# rfid1.net
KiCad netlist of a schematic drawn in EAGLE
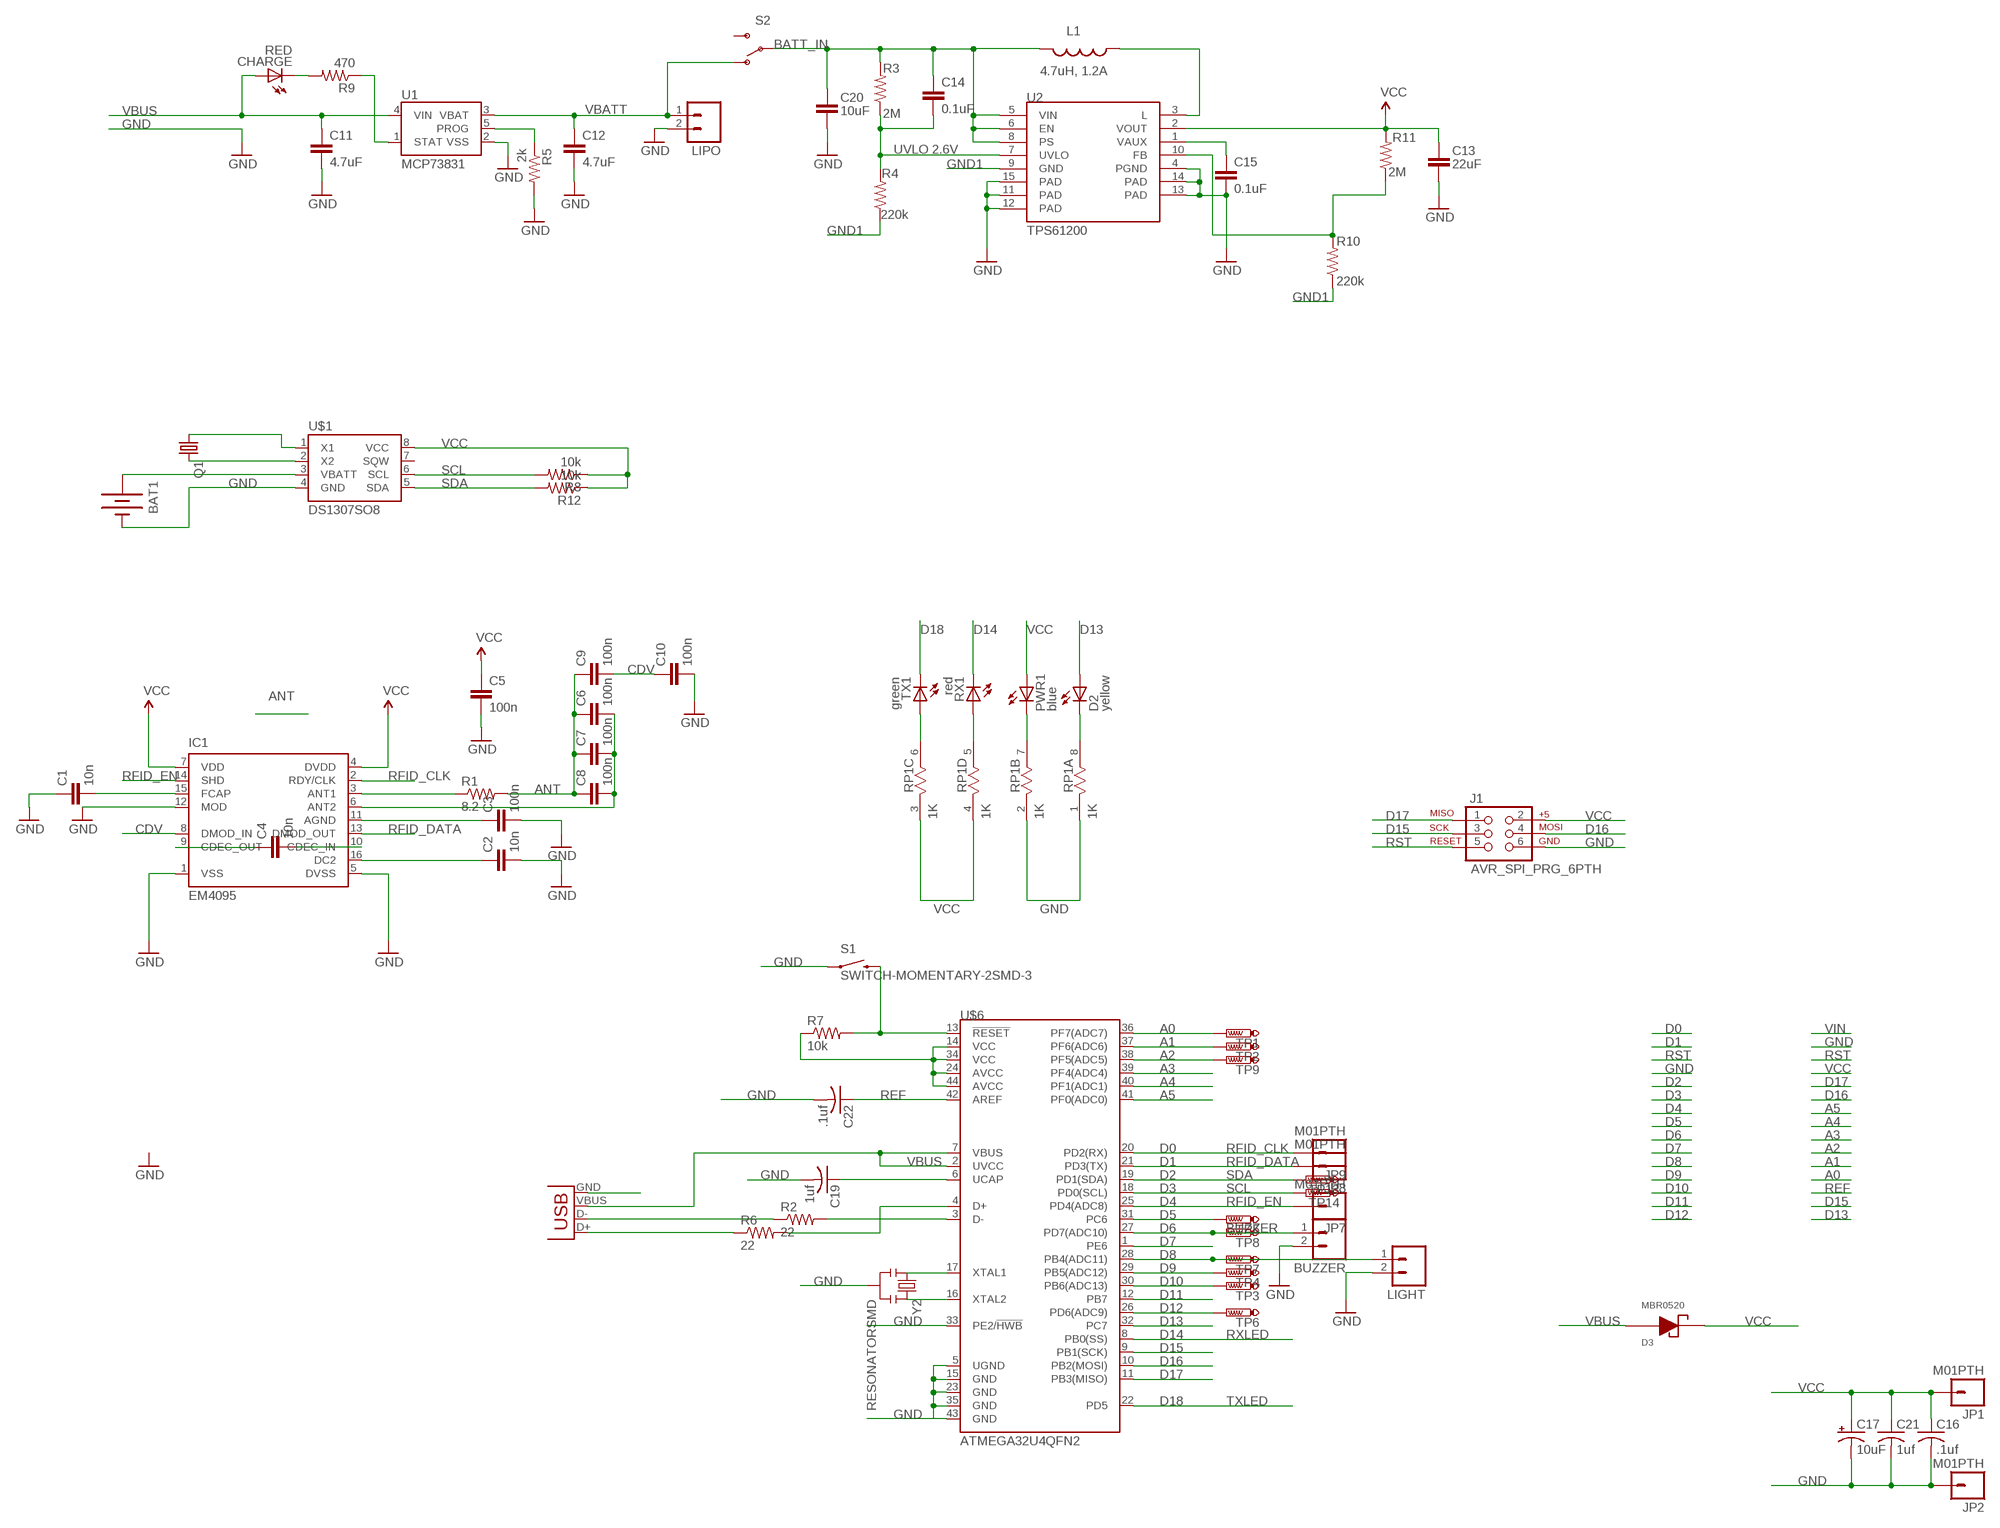
[diagram p0: schematic, sheet 1]

(export (version "E")
  (design (tool "Eeschema 10.0.6"))
  (components
    (comp (ref "BAT1")
      (value "BATTERY12MM")
      (footprint "eagle-import:BATTCON_12MM")
      (libsource (lib "eagle-import") (part "BATTERY12MM"))
    )
    (comp (ref "BUZZER")
      (value "M02PTH")
      (footprint "eagle-import:1X02")
      (libsource (lib "eagle-import") (part "M02PTH"))
    )
    (comp (ref "C1")
      (value "10n")
      (footprint "eagle-import:0805")
      (libsource (lib "eagle-import") (part "SparkFun-Passives_CAP0805"))
    )
    (comp (ref "C2")
      (value "10n")
      (footprint "eagle-import:0805")
      (libsource (lib "eagle-import") (part "SparkFun-Passives_CAP0805"))
    )
    (comp (ref "C3")
      (value "100n")
      (footprint "eagle-import:0805")
      (libsource (lib "eagle-import") (part "SparkFun-Passives_CAP0805"))
    )
    (comp (ref "C4")
      (value "10n")
      (footprint "eagle-import:0805")
      (libsource (lib "eagle-import") (part "SparkFun-Passives_CAP0805"))
    )
    (comp (ref "C5")
      (value "100n")
      (footprint "eagle-import:0805")
      (libsource (lib "eagle-import") (part "SparkFun-Passives_CAP0805"))
    )
    (comp (ref "C6")
      (value "100n")
      (footprint "eagle-import:0805")
      (libsource (lib "eagle-import") (part "SparkFun-Passives_CAP0805"))
    )
    (comp (ref "C7")
      (value "100n")
      (footprint "eagle-import:0805")
      (libsource (lib "eagle-import") (part "SparkFun-Passives_CAP0805"))
    )
    (comp (ref "C8")
      (value "100n")
      (footprint "eagle-import:0805")
      (libsource (lib "eagle-import") (part "SparkFun-Passives_CAP0805"))
    )
    (comp (ref "C9")
      (value "100n")
      (footprint "eagle-import:0805")
      (libsource (lib "eagle-import") (part "SparkFun-Passives_CAP0805"))
    )
    (comp (ref "C10")
      (value "100n")
      (footprint "eagle-import:0805")
      (libsource (lib "eagle-import") (part "SparkFun-Passives_CAP0805"))
    )
    (comp (ref "C11")
      (value "4.7uF")
      (footprint "eagle-import:0603-CAP")
      (libsource (lib "eagle-import") (part "CAP0603-CAP"))
    )
    (comp (ref "C12")
      (value "4.7uF")
      (footprint "eagle-import:0603-CAP")
      (libsource (lib "eagle-import") (part "CAP0603-CAP"))
    )
    (comp (ref "C13")
      (value "22uF")
      (footprint "eagle-import:0805")
      (libsource (lib "eagle-import") (part "CAP0805"))
    )
    (comp (ref "C14")
      (value "0.1uF")
      (footprint "eagle-import:0603-CAP")
      (libsource (lib "eagle-import") (part "CAP0603-CAP"))
    )
    (comp (ref "C15")
      (value "0.1uF")
      (footprint "eagle-import:0603-CAP")
      (libsource (lib "eagle-import") (part "CAP0603-CAP"))
    )
    (comp (ref "C16")
      (value ".1uf")
      (footprint "eagle-import:C0603")
      (libsource (lib "eagle-import") (part "C-USC0603"))
    )
    (comp (ref "C17")
      (value "10uF")
      (footprint "eagle-import:EIA3216")
      (libsource (lib "eagle-import") (part "CAP_POL1206"))
    )
    (comp (ref "C19")
      (value "1uf")
      (footprint "eagle-import:C0603")
      (libsource (lib "eagle-import") (part "C-USC0603"))
    )
    (comp (ref "C20")
      (value "10uF")
      (footprint "eagle-import:1206")
      (libsource (lib "eagle-import") (part "CAP1206"))
    )
    (comp (ref "C21")
      (value "1uf")
      (footprint "eagle-import:C0603")
      (libsource (lib "eagle-import") (part "C-USC0603"))
    )
    (comp (ref "C22")
      (value ".1uf")
      (footprint "eagle-import:C0603")
      (libsource (lib "eagle-import") (part "C-USC0603"))
    )
    (comp (ref "CHARGE")
      (value "RED")
      (footprint "eagle-import:CHIPLED_0805")
      (libsource (lib "eagle-import") (part "LEDCHIPLED_0805"))
    )
    (comp (ref "D2")
      (value "yellow")
      (footprint "eagle-import:CHIPLED_0805")
      (libsource (lib "eagle-import") (part "LEDCHIPLED_0805"))
    )
    (comp (ref "D3")
      (value "MBR0520")
      (footprint "eagle-import:SOD-123")
      (libsource (lib "eagle-import") (part "MBR0520"))
    )
    (comp (ref "IC1")
      (value "EM4095")
      (footprint "eagle-import:SO16")
      (libsource (lib "eagle-import") (part "EM4095"))
    )
    (comp (ref "J1")
      (value "AVR_SPI_PRG_6PTH")
      (footprint "eagle-import:2X3")
      (libsource (lib "eagle-import") (part "AVR_SPI_PRG_6PTH"))
    )
    (comp (ref "JP1")
      (value "M01PTH")
      (footprint "eagle-import:1X01")
      (libsource (lib "eagle-import") (part "M01PTH"))
    )
    (comp (ref "JP2")
      (value "M01PTH")
      (footprint "eagle-import:1X01")
      (libsource (lib "eagle-import") (part "M01PTH"))
    )
    (comp (ref "JP7")
      (value "M01PTH")
      (footprint "eagle-import:1X01")
      (libsource (lib "eagle-import") (part "M01PTH"))
    )
    (comp (ref "JP8")
      (value "M01PTH")
      (footprint "eagle-import:1X01")
      (libsource (lib "eagle-import") (part "M01PTH"))
    )
    (comp (ref "JP9")
      (value "M01PTH")
      (footprint "eagle-import:1X01")
      (libsource (lib "eagle-import") (part "M01PTH"))
    )
    (comp (ref "L1")
      (value "4.7uH, 1.2A")
      (footprint "eagle-import:CDRH2D09")
      (libsource (lib "eagle-import") (part "INDUCTOR."))
    )
    (comp (ref "LIGHT")
      (value "M02PTH")
      (footprint "eagle-import:1X02")
      (libsource (lib "eagle-import") (part "M02PTH"))
    )
    (comp (ref "LIPO")
      (value "M02-JST-2-PTH-NO_SILK")
      (footprint "eagle-import:JST-2-PTH-NS")
      (libsource (lib "eagle-import") (part "M02-JST-2-PTH-NO_SILK"))
    )
    (comp (ref "PWR1")
      (value "blue")
      (footprint "eagle-import:CHIPLED_0805")
      (libsource (lib "eagle-import") (part "LEDCHIPLED_0805"))
    )
    (comp (ref "Q1")
      (value "CRYSTALTC26H")
      (footprint "eagle-import:TC26H")
      (libsource (lib "eagle-import") (part "CRYSTALTC26H"))
    )
    (comp (ref "R1")
      (value "8.2")
      (footprint "eagle-import:0805")
      (libsource (lib "eagle-import") (part "SparkFun-Passives_RESISTOR0805-RES"))
    )
    (comp (ref "R2")
      (value "22")
      (footprint "eagle-import:0603-RES")
      (libsource (lib "eagle-import") (part "RESISTOR0603-RES"))
    )
    (comp (ref "R3")
      (value "2M")
      (footprint "eagle-import:0603-RES")
      (libsource (lib "eagle-import") (part "RESISTOR0603-RES"))
    )
    (comp (ref "R4")
      (value "220k")
      (footprint "eagle-import:0603-RES")
      (libsource (lib "eagle-import") (part "RESISTOR0603-RES"))
    )
    (comp (ref "R5")
      (value "2k")
      (footprint "eagle-import:0603-RES")
      (libsource (lib "eagle-import") (part "RESISTOR0603-RES"))
    )
    (comp (ref "R6")
      (value "22")
      (footprint "eagle-import:0603-RES")
      (libsource (lib "eagle-import") (part "RESISTOR0603-RES"))
    )
    (comp (ref "R7")
      (value "10k")
      (footprint "eagle-import:0603-RES")
      (libsource (lib "eagle-import") (part "RESISTOR0603-RES"))
    )
    (comp (ref "R8")
      (value "10k")
      (footprint "eagle-import:0603-RES")
      (libsource (lib "eagle-import") (part "RESISTOR0603-RES"))
    )
    (comp (ref "R9")
      (value "470")
      (footprint "eagle-import:0603-RES")
      (libsource (lib "eagle-import") (part "RESISTOR0603-RES"))
    )
    (comp (ref "R10")
      (value "220k")
      (footprint "eagle-import:0603-RES")
      (libsource (lib "eagle-import") (part "RESISTOR0603-RES"))
    )
    (comp (ref "R11")
      (value "2M")
      (footprint "eagle-import:0603-RES")
      (libsource (lib "eagle-import") (part "RESISTOR0603-RES"))
    )
    (comp (ref "R12")
      (value "10k")
      (footprint "eagle-import:0603-RES")
      (libsource (lib "eagle-import") (part "RESISTOR0603-RES"))
    )
    (comp (ref "RP1")
      (value "1K")
      (footprint "eagle-import:RES4NT")
      (libsource (lib "eagle-import") (part "RES4NT"))
    )
    (comp (ref "RX1")
      (value "red")
      (footprint "eagle-import:CHIPLED_0805")
      (libsource (lib "eagle-import") (part "LEDCHIPLED_0805"))
    )
    (comp (ref "S1")
      (value "SWITCH-MOMENTARY-2SMD-3")
      (footprint "eagle-import:TACTILE_SWITCH_SMD-3")
      (libsource (lib "eagle-import") (part "SWITCH-MOMENTARY-2SMD-3"))
    )
    (comp (ref "S2")
      (value "SWITCH-SPDTPTH")
      (footprint "eagle-import:SWITCH-SPDT")
      (libsource (lib "eagle-import") (part "SWITCH-SPDTPTH"))
    )
    (comp (ref "TP1")
      (value "PTR1TP14R")
      (footprint "eagle-import:TP14R")
      (libsource (lib "eagle-import") (part "PTR1TP14R"))
    )
    (comp (ref "TP2")
      (value "PTR1TP14R")
      (footprint "eagle-import:TP14R")
      (libsource (lib "eagle-import") (part "PTR1TP14R"))
    )
    (comp (ref "TP3")
      (value "PTR1TP14R")
      (footprint "eagle-import:TP14R")
      (libsource (lib "eagle-import") (part "PTR1TP14R"))
    )
    (comp (ref "TP4")
      (value "PTR1TP14R")
      (footprint "eagle-import:TP14R")
      (libsource (lib "eagle-import") (part "PTR1TP14R"))
    )
    (comp (ref "TP5")
      (value "PTR1TP14R")
      (footprint "eagle-import:TP14R")
      (libsource (lib "eagle-import") (part "PTR1TP14R"))
    )
    (comp (ref "TP6")
      (value "PTR1TP14R")
      (footprint "eagle-import:TP14R")
      (libsource (lib "eagle-import") (part "PTR1TP14R"))
    )
    (comp (ref "TP7")
      (value "PTR1TP14R")
      (footprint "eagle-import:TP14R")
      (libsource (lib "eagle-import") (part "PTR1TP14R"))
    )
    (comp (ref "TP8")
      (value "PTR1TP14R")
      (footprint "eagle-import:TP14R")
      (libsource (lib "eagle-import") (part "PTR1TP14R"))
    )
    (comp (ref "TP9")
      (value "PTR1TP14R")
      (footprint "eagle-import:TP14R")
      (libsource (lib "eagle-import") (part "PTR1TP14R"))
    )
    (comp (ref "TP13")
      (value "PTR1TP14R")
      (footprint "eagle-import:TP14R")
      (libsource (lib "eagle-import") (part "PTR1TP14R"))
    )
    (comp (ref "TP14")
      (value "PTR1TP14R")
      (footprint "eagle-import:TP14R")
      (libsource (lib "eagle-import") (part "PTR1TP14R"))
    )
    (comp (ref "TX1")
      (value "green")
      (footprint "eagle-import:CHIPLED_0805")
      (libsource (lib "eagle-import") (part "LEDCHIPLED_0805"))
    )
    (comp (ref "U$1")
      (value "DS1307SO8")
      (footprint "eagle-import:SO08")
      (libsource (lib "eagle-import") (part "DS1307SO8"))
    )
    (comp (ref "U$6")
      (value "ATMEGA32U4QFN2")
      (footprint "eagle-import:QFN-44-NOPAD")
      (libsource (lib "eagle-import") (part "ATMEGA32U4QFN2"))
    )
    (comp (ref "U1")
      (value "MCP73831")
      (footprint "eagle-import:SOT23-5")
      (libsource (lib "eagle-import") (part "MCP73831"))
    )
    (comp (ref "U2")
      (value "TPS61200")
      (footprint "eagle-import:QFN-10_PAD")
      (libsource (lib "eagle-import") (part "TPS61200"))
    )
    (comp (ref "X2")
      (value "USB-MICROB")
      (footprint "eagle-import:USB-MICROB")
      (libsource (lib "eagle-import") (part "USB-MICROB"))
    )
    (comp (ref "Y2")
      (value "RESONATORSMD")
      (footprint "eagle-import:RESONATOR-SMD")
      (libsource (lib "eagle-import") (part "RESONATORSMD"))
    )
  )
  (nets
    (net (code "1") (name "/A0") (class "Default")
      (node (ref "TP1") (pin "TP") (pinfunction "TP_TP") (pintype "input"))
      (node (ref "U$6") (pin "36") (pinfunction "PF7(ADC7)_36") (pintype "bidirectional"))
    )
    (net (code "2") (name "/A1") (class "Default")
      (node (ref "TP2") (pin "TP") (pinfunction "TP_TP") (pintype "input"))
      (node (ref "U$6") (pin "37") (pinfunction "PF6(ADC6)_37") (pintype "bidirectional"))
    )
    (net (code "3") (name "/A2") (class "Default")
      (node (ref "TP9") (pin "TP") (pinfunction "TP_TP") (pintype "input"))
      (node (ref "U$6") (pin "38") (pinfunction "PF5(ADC5)_38") (pintype "bidirectional"))
    )
    (net (code "4") (name "/A3") (class "Default")
      (node (ref "U$6") (pin "39") (pinfunction "PF4(ADC4)_39") (pintype "bidirectional"))
    )
    (net (code "5") (name "/A4") (class "Default")
      (node (ref "U$6") (pin "40") (pinfunction "PF1(ADC1)_40") (pintype "bidirectional"))
    )
    (net (code "6") (name "/A5") (class "Default")
      (node (ref "U$6") (pin "41") (pinfunction "PF0(ADC0)_41") (pintype "bidirectional"))
    )
    (net (code "7") (name "/ANT") (class "Default")
      (node (ref "C6") (pin "1") (pinfunction "1_1") (pintype "passive"))
      (node (ref "C7") (pin "1") (pinfunction "1_1") (pintype "passive"))
      (node (ref "C8") (pin "1") (pinfunction "1_1") (pintype "passive"))
      (node (ref "C9") (pin "1") (pinfunction "1_1") (pintype "passive"))
      (node (ref "R1") (pin "2") (pinfunction "2_2") (pintype "passive"))
    )
    (net (code "8") (name "/BATT_IN") (class "Default")
      (node (ref "C14") (pin "1") (pinfunction "1_1") (pintype "passive"))
      (node (ref "C20") (pin "1") (pinfunction "1_1") (pintype "passive"))
      (node (ref "L1") (pin "P$2") (pinfunction "2_P$2") (pintype "passive"))
      (node (ref "R3") (pin "2") (pinfunction "2_2") (pintype "passive"))
      (node (ref "S2") (pin "2") (pinfunction "P_2") (pintype "passive"))
      (node (ref "U2") (pin "5") (pinfunction "VIN_5") (pintype "power_in"))
      (node (ref "U2") (pin "6") (pinfunction "EN_6") (pintype "input"))
      (node (ref "U2") (pin "8") (pinfunction "PS_8") (pintype "input"))
    )
    (net (code "9") (name "/CDV") (class "Default")
      (node (ref "C10") (pin "1") (pinfunction "1_1") (pintype "passive"))
      (node (ref "C9") (pin "2") (pinfunction "2_2") (pintype "passive"))
      (node (ref "IC1") (pin "8") (pinfunction "DMOD_IN_8") (pintype "input"))
    )
    (net (code "15") (name "/D5") (class "Default")
      (node (ref "TP5") (pin "TP") (pinfunction "TP_TP") (pintype "input"))
      (node (ref "U$6") (pin "31") (pinfunction "PC6_31") (pintype "bidirectional"))
    )
    (net (code "16") (name "/D6") (class "Default")
      (node (ref "BUZZER") (pin "1") (pinfunction "1_1") (pintype "passive"))
      (node (ref "TP8") (pin "TP") (pinfunction "TP_TP") (pintype "input"))
      (node (ref "U$6") (pin "27") (pinfunction "PD7(ADC10)_27") (pintype "bidirectional"))
    )
    (net (code "17") (name "/D7") (class "Default")
      (node (ref "U$6") (pin "1") (pinfunction "PE6_1") (pintype "bidirectional"))
    )
    (net (code "18") (name "/D8") (class "Default")
      (node (ref "LIGHT") (pin "1") (pinfunction "1_1") (pintype "passive"))
      (node (ref "TP7") (pin "TP") (pinfunction "TP_TP") (pintype "input"))
      (node (ref "U$6") (pin "28") (pinfunction "PB4(ADC11)_28") (pintype "bidirectional"))
    )
    (net (code "19") (name "/D9") (class "Default")
      (node (ref "TP4") (pin "TP") (pinfunction "TP_TP") (pintype "input"))
      (node (ref "U$6") (pin "29") (pinfunction "PB5(ADC12)_29") (pintype "bidirectional"))
    )
    (net (code "20") (name "/D10") (class "Default")
      (node (ref "TP3") (pin "TP") (pinfunction "TP_TP") (pintype "input"))
      (node (ref "U$6") (pin "30") (pinfunction "PB6(ADC13)_30") (pintype "bidirectional"))
    )
    (net (code "21") (name "/D11") (class "Default")
      (node (ref "U$6") (pin "12") (pinfunction "PB7_12") (pintype "bidirectional"))
    )
    (net (code "22") (name "/D12") (class "Default")
      (node (ref "TP6") (pin "TP") (pinfunction "TP_TP") (pintype "input"))
      (node (ref "U$6") (pin "26") (pinfunction "PD6(ADC9)_26") (pintype "bidirectional"))
    )
    (net (code "23") (name "/D13") (class "Default")
      (node (ref "D2") (pin "A") (pinfunction "A_A") (pintype "passive"))
      (node (ref "U$6") (pin "32") (pinfunction "PC7_32") (pintype "bidirectional"))
    )
    (net (code "24") (name "/D14") (class "Default")
      (node (ref "RX1") (pin "C") (pinfunction "C_C") (pintype "passive"))
      (node (ref "U$6") (pin "8") (pinfunction "PB0(SS)_8") (pintype "bidirectional"))
    )
    (net (code "25") (name "/D15") (class "Default")
      (node (ref "J1") (pin "3") (pinfunction "3_3") (pintype "passive"))
      (node (ref "U$6") (pin "9") (pinfunction "PB1(SCK)_9") (pintype "bidirectional"))
    )
    (net (code "26") (name "/D16") (class "Default")
      (node (ref "J1") (pin "4") (pinfunction "4_4") (pintype "passive"))
      (node (ref "U$6") (pin "10") (pinfunction "PB2(MOSI)_10") (pintype "bidirectional"))
    )
    (net (code "27") (name "/D17") (class "Default")
      (node (ref "J1") (pin "1") (pinfunction "1_1") (pintype "passive"))
      (node (ref "U$6") (pin "11") (pinfunction "PB3(MISO)_11") (pintype "bidirectional"))
    )
    (net (code "28") (name "/D18") (class "Default")
      (node (ref "TX1") (pin "C") (pinfunction "C_C") (pintype "passive"))
      (node (ref "U$6") (pin "22") (pinfunction "PD5_22") (pintype "bidirectional"))
    )
    (net (code "29") (name "/GND1") (class "Default")
      (node (ref "R10") (pin "1") (pinfunction "1_1") (pintype "passive"))
      (node (ref "R4") (pin "1") (pinfunction "1_1") (pintype "passive"))
      (node (ref "U2") (pin "9") (pinfunction "GND_9") (pintype "power_in"))
    )
    (net (code "30") (name "/REF") (class "Default")
      (node (ref "C22") (pin "1") (pinfunction "1_1") (pintype "passive"))
      (node (ref "U$6") (pin "42") (pinfunction "AREF_42") (pintype "bidirectional"))
    )
    (net (code "31") (name "/RFID_CLK") (class "Default")
      (node (ref "IC1") (pin "2") (pinfunction "RDY/CLK_2") (pintype "output"))
      (node (ref "JP9") (pin "1") (pinfunction "1_1") (pintype "passive"))
      (node (ref "U$6") (pin "20") (pinfunction "PD2(RX)_20") (pintype "bidirectional"))
    )
    (net (code "32") (name "/RFID_DATA") (class "Default")
      (node (ref "IC1") (pin "13") (pinfunction "DMOD_OUT_13") (pintype "output"))
      (node (ref "JP8") (pin "1") (pinfunction "1_1") (pintype "passive"))
      (node (ref "U$6") (pin "21") (pinfunction "PD3(TX)_21") (pintype "bidirectional"))
    )
    (net (code "33") (name "/RFID_EN") (class "Default")
      (node (ref "IC1") (pin "14") (pinfunction "SHD_14") (pintype "input"))
      (node (ref "JP7") (pin "1") (pinfunction "1_1") (pintype "passive"))
      (node (ref "U$6") (pin "25") (pinfunction "PD4(ADC8)_25") (pintype "bidirectional"))
    )
    (net (code "34") (name "/RST") (class "Default")
      (node (ref "J1") (pin "5") (pinfunction "5_5") (pintype "passive"))
      (node (ref "R7") (pin "2") (pinfunction "2_2") (pintype "passive"))
      (node (ref "S1") (pin "P$2") (pinfunction "2_P$2") (pintype "passive"))
      (node (ref "U$6") (pin "13") (pinfunction "~{RESET}_13") (pintype "bidirectional"))
    )
    (net (code "35") (name "/SCL") (class "Default")
      (node (ref "R8") (pin "2") (pinfunction "2_2") (pintype "passive"))
      (node (ref "TP14") (pin "TP") (pinfunction "TP_TP") (pintype "input"))
      (node (ref "U$1") (pin "6") (pinfunction "SCL_6") (pintype "bidirectional"))
      (node (ref "U$6") (pin "18") (pinfunction "PD0(SCL)_18") (pintype "bidirectional"))
    )
    (net (code "36") (name "/SDA") (class "Default")
      (node (ref "R12") (pin "2") (pinfunction "2_2") (pintype "passive"))
      (node (ref "TP13") (pin "TP") (pinfunction "TP_TP") (pintype "input"))
      (node (ref "U$1") (pin "5") (pinfunction "SDA_5") (pintype "bidirectional"))
      (node (ref "U$6") (pin "19") (pinfunction "PD1(SDA)_19") (pintype "bidirectional"))
    )
    (net (code "37") (name "/VBATT") (class "Default")
      (node (ref "C12") (pin "1") (pinfunction "1_1") (pintype "passive"))
      (node (ref "LIPO") (pin "1") (pinfunction "1_1") (pintype "passive"))
      (node (ref "S2") (pin "1") (pinfunction "O_1") (pintype "passive"))
      (node (ref "U1") (pin "3") (pinfunction "VBAT_3") (pintype "power_in"))
    )
    (net (code "38") (name "/VBUS") (class "Default")
      (node (ref "C11") (pin "1") (pinfunction "1_1") (pintype "passive"))
      (node (ref "CHARGE") (pin "A") (pinfunction "A_A") (pintype "passive"))
      (node (ref "D3") (pin "2") (pinfunction "AN_2") (pintype "passive"))
      (node (ref "U$6") (pin "2") (pinfunction "UVCC_2") (pintype "bidirectional"))
      (node (ref "U$6") (pin "7") (pinfunction "VBUS_7") (pintype "bidirectional"))
      (node (ref "U1") (pin "4") (pinfunction "VIN_4") (pintype "power_in"))
      (node (ref "X2") (pin "VBUS") (pinfunction "VBUS_VBUS") (pintype "bidirectional"))
    )
    (net (code "40") (name "GND") (class "Default")
      (node (ref "BAT1") (pin "GND") (pinfunction "-_GND") (pintype "power_in"))
      (node (ref "BUZZER") (pin "2") (pinfunction "2_2") (pintype "passive"))
      (node (ref "C1") (pin "1") (pinfunction "1_1") (pintype "passive"))
      (node (ref "C10") (pin "2") (pinfunction "2_2") (pintype "passive"))
      (node (ref "C11") (pin "2") (pinfunction "2_2") (pintype "passive"))
      (node (ref "C12") (pin "2") (pinfunction "2_2") (pintype "passive"))
      (node (ref "C13") (pin "2") (pinfunction "2_2") (pintype "passive"))
      (node (ref "C15") (pin "2") (pinfunction "2_2") (pintype "passive"))
      (node (ref "C16") (pin "2") (pinfunction "2_2") (pintype "passive"))
      (node (ref "C17") (pin "C") (pinfunction "-_C") (pintype "passive"))
      (node (ref "C19") (pin "2") (pinfunction "2_2") (pintype "passive"))
      (node (ref "C2") (pin "2") (pinfunction "2_2") (pintype "passive"))
      (node (ref "C20") (pin "2") (pinfunction "2_2") (pintype "passive"))
      (node (ref "C21") (pin "2") (pinfunction "2_2") (pintype "passive"))
      (node (ref "C22") (pin "2") (pinfunction "2_2") (pintype "passive"))
      (node (ref "C3") (pin "2") (pinfunction "2_2") (pintype "passive"))
      (node (ref "C5") (pin "2") (pinfunction "2_2") (pintype "passive"))
      (node (ref "IC1") (pin "1") (pinfunction "VSS_1") (pintype "power_in"))
      (node (ref "IC1") (pin "12") (pinfunction "MOD_12") (pintype "input"))
      (node (ref "IC1") (pin "5") (pinfunction "DVSS_5") (pintype "power_in"))
      (node (ref "J1") (pin "6") (pinfunction "6_6") (pintype "passive"))
      (node (ref "JP2") (pin "1") (pinfunction "1_1") (pintype "passive"))
      (node (ref "LIGHT") (pin "2") (pinfunction "2_2") (pintype "passive"))
      (node (ref "LIPO") (pin "2") (pinfunction "2_2") (pintype "passive"))
      (node (ref "R5") (pin "2") (pinfunction "2_2") (pintype "passive"))
      (node (ref "RP1") (pin "1") (pinfunction "1_1") (pintype "passive"))
      (node (ref "RP1") (pin "2") (pinfunction "1_2") (pintype "passive"))
      (node (ref "S1") (pin "P$1") (pinfunction "1_P$1") (pintype "passive"))
      (node (ref "U$1") (pin "4") (pinfunction "GND_4") (pintype "bidirectional"))
      (node (ref "U$6") (pin "15") (pinfunction "GND_15") (pintype "bidirectional"))
      (node (ref "U$6") (pin "23") (pinfunction "GND_23") (pintype "bidirectional"))
      (node (ref "U$6") (pin "33") (pinfunction "PE2/~{HWB}_33") (pintype "bidirectional"))
      (node (ref "U$6") (pin "35") (pinfunction "GND_35") (pintype "bidirectional"))
      (node (ref "U$6") (pin "43") (pinfunction "GND_43") (pintype "bidirectional"))
      (node (ref "U$6") (pin "5") (pinfunction "UGND_5") (pintype "bidirectional"))
      (node (ref "U1") (pin "2") (pinfunction "VSS_2") (pintype "power_in"))
      (node (ref "U2") (pin "11") (pinfunction "PAD_11") (pintype "power_in"))
      (node (ref "U2") (pin "12") (pinfunction "PAD_12") (pintype "power_in"))
      (node (ref "U2") (pin "13") (pinfunction "PAD_13") (pintype "power_in"))
      (node (ref "U2") (pin "14") (pinfunction "PAD_14") (pintype "power_in"))
      (node (ref "U2") (pin "15") (pinfunction "PAD_15") (pintype "power_in"))
      (node (ref "U2") (pin "4") (pinfunction "PGND_4") (pintype "power_in"))
      (node (ref "X2") (pin "GND") (pinfunction "GND_GND") (pintype "bidirectional"))
      (node (ref "Y2") (pin "2") (pinfunction "2_2") (pintype "passive"))
    )
    (net (code "41") (name "Net-(BAT1-+)") (class "Default")
      (node (ref "BAT1") (pin "PWR@1") (pinfunction "+_PWR@1") (pintype "power_in"))
      (node (ref "U$1") (pin "3") (pinfunction "VBATT_3") (pintype "bidirectional"))
    )
    (net (code "42") (name "Net-(CHARGE-PadC)") (class "Default")
      (node (ref "CHARGE") (pin "C") (pinfunction "C_C") (pintype "passive"))
      (node (ref "R9") (pin "2") (pinfunction "2_2") (pintype "passive"))
    )
    (net (code "43") (name "Net-(IC1-AGND)") (class "Default")
      (node (ref "C3") (pin "1") (pinfunction "1_1") (pintype "passive"))
      (node (ref "IC1") (pin "11") (pinfunction "AGND_11") (pintype "power_in"))
    )
    (net (code "44") (name "Net-(IC1-ANT1)") (class "Default")
      (node (ref "IC1") (pin "3") (pinfunction "ANT1_3") (pintype "passive"))
      (node (ref "R1") (pin "1") (pinfunction "1_1") (pintype "passive"))
    )
    (net (code "45") (name "Net-(IC1-ANT2)") (class "Default")
      (node (ref "C6") (pin "2") (pinfunction "2_2") (pintype "passive"))
      (node (ref "C7") (pin "2") (pinfunction "2_2") (pintype "passive"))
      (node (ref "C8") (pin "2") (pinfunction "2_2") (pintype "passive"))
      (node (ref "IC1") (pin "6") (pinfunction "ANT2_6") (pintype "passive"))
    )
    (net (code "46") (name "Net-(IC1-CDEC_IN)") (class "Default")
      (node (ref "C4") (pin "2") (pinfunction "2_2") (pintype "passive"))
      (node (ref "IC1") (pin "10") (pinfunction "CDEC_IN_10") (pintype "input"))
    )
    (net (code "47") (name "Net-(IC1-CDEC_OUT)") (class "Default")
      (node (ref "C4") (pin "1") (pinfunction "1_1") (pintype "passive"))
      (node (ref "IC1") (pin "9") (pinfunction "CDEC_OUT_9") (pintype "output"))
    )
    (net (code "48") (name "Net-(IC1-DC2)") (class "Default")
      (node (ref "C2") (pin "1") (pinfunction "1_1") (pintype "passive"))
      (node (ref "IC1") (pin "16") (pinfunction "DC2_16") (pintype "passive"))
    )
    (net (code "49") (name "Net-(IC1-FCAP)") (class "Default")
      (node (ref "C1") (pin "2") (pinfunction "2_2") (pintype "passive"))
      (node (ref "IC1") (pin "15") (pinfunction "FCAP_15") (pintype "passive"))
    )
    (net (code "50") (name "Net-(L1-1)") (class "Default")
      (node (ref "L1") (pin "P$1") (pinfunction "1_P$1") (pintype "passive"))
      (node (ref "U2") (pin "3") (pinfunction "L_3") (pintype "passive"))
    )
    (net (code "51") (name "Net-(R2-Pad1)") (class "Default")
      (node (ref "R2") (pin "1") (pinfunction "1_1") (pintype "passive"))
      (node (ref "X2") (pin "D-") (pinfunction "D-_D-") (pintype "bidirectional"))
    )
    (net (code "52") (name "Net-(R6-Pad1)") (class "Default")
      (node (ref "R6") (pin "1") (pinfunction "1_1") (pintype "passive"))
      (node (ref "X2") (pin "D+") (pinfunction "D+_D+") (pintype "bidirectional"))
    )
    (net (code "53") (name "Net-(RP1A-2)") (class "Default")
      (node (ref "D2") (pin "C") (pinfunction "C_C") (pintype "passive"))
      (node (ref "RP1") (pin "8") (pinfunction "2_8") (pintype "passive"))
    )
    (net (code "54") (name "Net-(RP1B-2)") (class "Default")
      (node (ref "PWR1") (pin "C") (pinfunction "C_C") (pintype "passive"))
      (node (ref "RP1") (pin "7") (pinfunction "2_7") (pintype "passive"))
    )
    (net (code "55") (name "Net-(RP1C-2)") (class "Default")
      (node (ref "RP1") (pin "6") (pinfunction "2_6") (pintype "passive"))
      (node (ref "TX1") (pin "A") (pinfunction "A_A") (pintype "passive"))
    )
    (net (code "56") (name "Net-(RP1D-2)") (class "Default")
      (node (ref "RP1") (pin "5") (pinfunction "2_5") (pintype "passive"))
      (node (ref "RX1") (pin "A") (pinfunction "A_A") (pintype "passive"))
    )
    (net (code "57") (name "Net-(U$1-X1)") (class "Default")
      (node (ref "Q1") (pin "1") (pinfunction "1_1") (pintype "passive"))
      (node (ref "U$1") (pin "1") (pinfunction "X1_1") (pintype "bidirectional"))
    )
    (net (code "58") (name "Net-(U$1-X2)") (class "Default")
      (node (ref "Q1") (pin "2") (pinfunction "2_2") (pintype "passive"))
      (node (ref "U$1") (pin "2") (pinfunction "X2_2") (pintype "bidirectional"))
    )
    (net (code "59") (name "Net-(U$6-D+)") (class "Default")
      (node (ref "R6") (pin "2") (pinfunction "2_2") (pintype "passive"))
      (node (ref "U$6") (pin "4") (pinfunction "D+_4") (pintype "bidirectional"))
    )
    (net (code "60") (name "Net-(U$6-D-)") (class "Default")
      (node (ref "R2") (pin "2") (pinfunction "2_2") (pintype "passive"))
      (node (ref "U$6") (pin "3") (pinfunction "D-_3") (pintype "bidirectional"))
    )
    (net (code "61") (name "Net-(U$6-UCAP)") (class "Default")
      (node (ref "C19") (pin "1") (pinfunction "1_1") (pintype "passive"))
      (node (ref "U$6") (pin "6") (pinfunction "UCAP_6") (pintype "bidirectional"))
    )
    (net (code "62") (name "Net-(U$6-XTAL1)") (class "Default")
      (node (ref "U$6") (pin "17") (pinfunction "XTAL1_17") (pintype "bidirectional"))
      (node (ref "Y2") (pin "1") (pinfunction "1_1") (pintype "passive"))
    )
    (net (code "63") (name "Net-(U$6-XTAL2)") (class "Default")
      (node (ref "U$6") (pin "16") (pinfunction "XTAL2_16") (pintype "bidirectional"))
      (node (ref "Y2") (pin "3") (pinfunction "3_3") (pintype "passive"))
    )
    (net (code "64") (name "Net-(U1-PROG)") (class "Default")
      (node (ref "R5") (pin "1") (pinfunction "1_1") (pintype "passive"))
      (node (ref "U1") (pin "5") (pinfunction "PROG_5") (pintype "input"))
    )
    (net (code "65") (name "Net-(U1-STAT)") (class "Default")
      (node (ref "R9") (pin "1") (pinfunction "1_1") (pintype "passive"))
      (node (ref "U1") (pin "1") (pinfunction "STAT_1") (pintype "output"))
    )
    (net (code "66") (name "Net-(U2-FB)") (class "Default")
      (node (ref "R10") (pin "2") (pinfunction "2_2") (pintype "passive"))
      (node (ref "R11") (pin "1") (pinfunction "1_1") (pintype "passive"))
      (node (ref "U2") (pin "10") (pinfunction "FB_10") (pintype "passive"))
    )
    (net (code "67") (name "Net-(U2-UVLO)") (class "Default")
      (node (ref "C14") (pin "2") (pinfunction "2_2") (pintype "passive"))
      (node (ref "R3") (pin "1") (pinfunction "1_1") (pintype "passive"))
      (node (ref "R4") (pin "2") (pinfunction "2_2") (pintype "passive"))
      (node (ref "U2") (pin "7") (pinfunction "UVLO_7") (pintype "passive"))
    )
    (net (code "68") (name "Net-(U2-VAUX)") (class "Default")
      (node (ref "C15") (pin "1") (pinfunction "1_1") (pintype "passive"))
      (node (ref "U2") (pin "1") (pinfunction "VAUX_1") (pintype "passive"))
    )
    (net (code "69") (name "VCC") (class "Default")
      (node (ref "C13") (pin "1") (pinfunction "1_1") (pintype "passive"))
      (node (ref "C16") (pin "1") (pinfunction "1_1") (pintype "passive"))
      (node (ref "C17") (pin "A") (pinfunction "+_A") (pintype "passive"))
      (node (ref "C21") (pin "1") (pinfunction "1_1") (pintype "passive"))
      (node (ref "C5") (pin "1") (pinfunction "1_1") (pintype "passive"))
      (node (ref "D3") (pin "1") (pinfunction "CA_1") (pintype "passive"))
      (node (ref "IC1") (pin "4") (pinfunction "DVDD_4") (pintype "power_in"))
      (node (ref "IC1") (pin "7") (pinfunction "VDD_7") (pintype "power_in"))
      (node (ref "J1") (pin "2") (pinfunction "2_2") (pintype "passive"))
      (node (ref "JP1") (pin "1") (pinfunction "1_1") (pintype "passive"))
      (node (ref "PWR1") (pin "A") (pinfunction "A_A") (pintype "passive"))
      (node (ref "R11") (pin "2") (pinfunction "2_2") (pintype "passive"))
      (node (ref "R12") (pin "1") (pinfunction "1_1") (pintype "passive"))
      (node (ref "R7") (pin "1") (pinfunction "1_1") (pintype "passive"))
      (node (ref "R8") (pin "1") (pinfunction "1_1") (pintype "passive"))
      (node (ref "RP1") (pin "3") (pinfunction "1_3") (pintype "passive"))
      (node (ref "RP1") (pin "4") (pinfunction "1_4") (pintype "passive"))
      (node (ref "U$1") (pin "8") (pinfunction "VCC_8") (pintype "bidirectional"))
      (node (ref "U$6") (pin "14") (pinfunction "VCC_14") (pintype "bidirectional"))
      (node (ref "U$6") (pin "24") (pinfunction "AVCC_24") (pintype "bidirectional"))
      (node (ref "U$6") (pin "34") (pinfunction "VCC_34") (pintype "bidirectional"))
      (node (ref "U$6") (pin "44") (pinfunction "AVCC_44") (pintype "bidirectional"))
      (node (ref "U2") (pin "2") (pinfunction "VOUT_2") (pintype "passive"))
    )
    (net (code "70") (name "unconnected-(S2-S-Pad3)") (class "Default")
      (node (ref "S2") (pin "3") (pinfunction "S_3") (pintype "passive"))
    )
    (net (code "71") (name "unconnected-(U$1-SQW-Pad7)") (class "Default")
      (node (ref "U$1") (pin "7") (pinfunction "SQW_7") (pintype "bidirectional"))
    )
  )
)
